# IO_Peripherals.net
KiCad netlist of a schematic drawn in Altium Designer
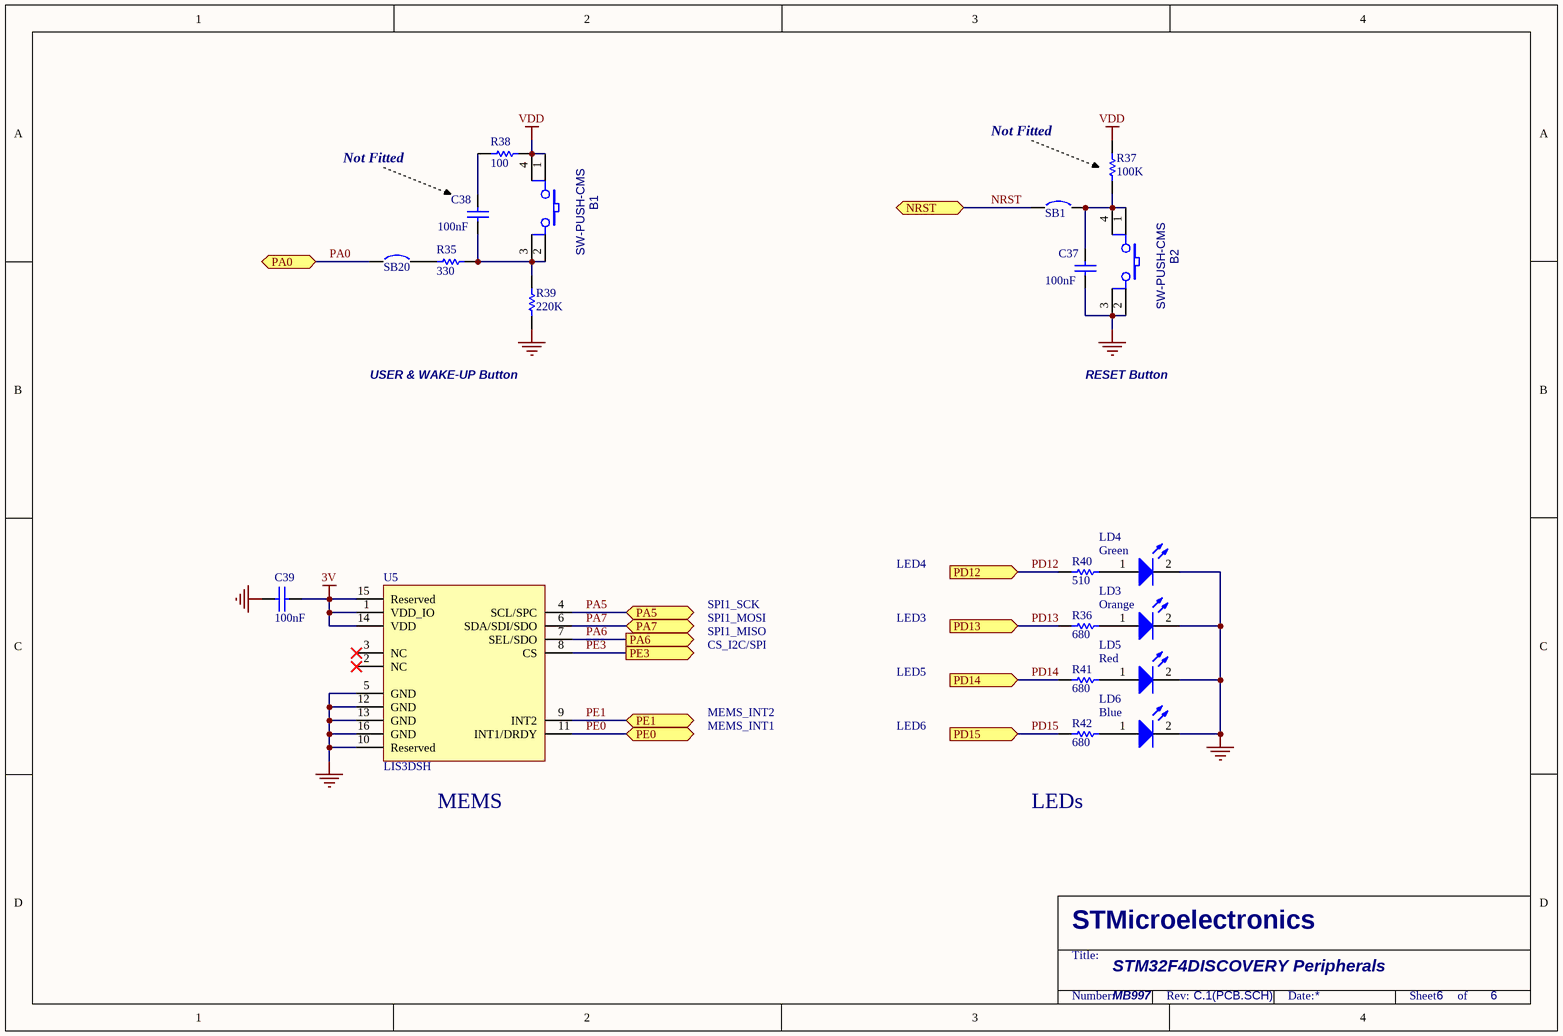
[diagram p0: IO Peripherals.SchDoc]

(export (version "E")
  (design (tool "Eeschema 10.0.6"))
  (components
    (comp (ref "B1")
      (value "SW-PUSH-CMS")
      (footprint "BP1CMS")
      (description "Non-Open Push-Button 0.1A 24V")
      (libsource (lib "MB913_1") (part "SW-PUSH-CMS"))
    )
    (comp (ref "B2")
      (value "SW-PUSH-CMS")
      (footprint "BP1CMS")
      (description "Non-Open Push-Button 0.1A 24V")
      (libsource (lib "MB913_1") (part "SW-PUSH-CMS"))
    )
    (comp (ref "C37")
      (value "100nF")
      (footprint "0603C")
      (description "Capacitor")
      (fields (field (name "PUBLISHER") "Altium Limited"))
      (libsource (lib "Miscellaneous Devices") (part "CAP"))
    )
    (comp (ref "C38")
      (value "100nF")
      (footprint "0603C")
      (description "Capacitor")
      (fields (field (name "PUBLISHER") "Altium Limited"))
      (libsource (lib "Miscellaneous Devices") (part "CAP"))
    )
    (comp (ref "C39")
      (value "100nF")
      (footprint "0402C")
      (description "Capacitor")
      (libsource (lib "*") (part "CAP"))
    )
    (comp (ref "LD3")
      (value "Orange")
      (footprint "0603D")
      (description "Typical RED, GREEN, YELLOW, AMBER GaAs LED")
      (fields (field (name "PUBLISHER") "Altium Limited"))
      (libsource (lib "Miscellaneous Devices") (part "LED2"))
    )
    (comp (ref "LD4")
      (value "Green")
      (footprint "0603D")
      (description "Typical RED, GREEN, YELLOW, AMBER GaAs LED")
      (fields (field (name "PUBLISHER") "Altium Limited"))
      (libsource (lib "Miscellaneous Devices") (part "LED2"))
    )
    (comp (ref "LD5")
      (value "Red")
      (footprint "0603D")
      (description "Typical RED, GREEN, YELLOW, AMBER GaAs LED")
      (fields (field (name "PUBLISHER") "Altium Limited"))
      (libsource (lib "Miscellaneous Devices") (part "LED2"))
    )
    (comp (ref "LD6")
      (value "Blue")
      (footprint "0603D")
      (description "Typical RED, GREEN, YELLOW, AMBER GaAs LED")
      (fields (field (name "PUBLISHER") "Altium Limited"))
      (libsource (lib "Miscellaneous Devices") (part "LED2"))
    )
    (comp (ref "R35")
      (value "330")
      (footprint "0402R")
      (description "Resistor")
      (fields (field (name "PUBLISHER") "Altium Limited"))
      (libsource (lib "Miscellaneous Devices") (part "res1"))
    )
    (comp (ref "R36")
      (value "680")
      (footprint "0603R")
      (description "Resistor")
      (fields (field (name "PUBLISHER") "Altium Limited"))
      (libsource (lib "Miscellaneous Devices") (part "Res1"))
    )
    (comp (ref "R37")
      (value "100K")
      (footprint "0402R")
      (description "Resistor")
      (fields (field (name "PUBLISHER") "Altium Limited"))
      (libsource (lib "Miscellaneous Devices") (part "res1"))
    )
    (comp (ref "R38")
      (value "100")
      (footprint "0402R")
      (description "Resistor")
      (fields (field (name "PUBLISHER") "Altium Limited"))
      (libsource (lib "Miscellaneous Devices") (part "res1"))
    )
    (comp (ref "R39")
      (value "220K")
      (description "Resistor")
      (fields (field (name "PUBLISHER") "Altium Limited"))
      (libsource (lib "Miscellaneous Devices") (part "res1"))
    )
    (comp (ref "R40")
      (value "510")
      (footprint "0603R")
      (description "Resistor")
      (fields (field (name "PUBLISHER") "Altium Limited"))
      (libsource (lib "Miscellaneous Devices") (part "Res1"))
    )
    (comp (ref "R41")
      (value "680")
      (footprint "0603R")
      (description "Resistor")
      (fields (field (name "PUBLISHER") "Altium Limited"))
      (libsource (lib "Miscellaneous Devices") (part "Res1"))
    )
    (comp (ref "R42")
      (value "680")
      (footprint "0603R")
      (description "Resistor")
      (fields (field (name "PUBLISHER") "Altium Limited"))
      (libsource (lib "Miscellaneous Devices") (part "Res1"))
    )
    (comp (ref "SB1")
      (value "Circuit Breaker")
      (footprint "JP2_SMD")
      (fields (field (name "PUBLISHER") "Altium Limited"))
      (libsource (lib "MB915") (part "Circuit Breaker"))
    )
    (comp (ref "SB20")
      (value "Circuit Breaker")
      (footprint "JP2_SMD")
      (fields (field (name "PUBLISHER") "Altium Limited"))
      (libsource (lib "MB915") (part "Circuit Breaker"))
    )
    (comp (ref "U5")
      (value "LIS3DSH")
      (footprint "LGA16(3*3)")
      (description "MEMS motion sensor 3-axis - ±2g to ±16g digital output accelerometer")
      (libsource (lib "MB997") (part "LIS3DSH"))
    )
  )
  (nets
    (net (code "1") (name "/NRST") (class "Default")
      (node (ref "SB1") (pin "1") (pinfunction "1_1") (pintype "passive"))
    )
    (net (code "2") (name "/PA0") (class "Default")
      (node (ref "SB20") (pin "1") (pinfunction "1_1") (pintype "passive"))
    )
    (net (code "3") (name "/PA5") (class "Default")
      (node (ref "U5") (pin "4") (pinfunction "SCL/SPC_4") (pintype "passive"))
    )
    (net (code "4") (name "/PA6") (class "Default")
      (node (ref "U5") (pin "7") (pinfunction "SEL/SDO_7") (pintype "passive"))
    )
    (net (code "5") (name "/PA7") (class "Default")
      (node (ref "U5") (pin "6") (pinfunction "SDA/SDI/SDO_6") (pintype "passive"))
    )
    (net (code "6") (name "/PD12") (class "Default")
      (node (ref "R40") (pin "2") (pinfunction "2_2") (pintype "passive"))
    )
    (net (code "7") (name "/PD13") (class "Default")
      (node (ref "R36") (pin "2") (pinfunction "2_2") (pintype "passive"))
    )
    (net (code "8") (name "/PD14") (class "Default")
      (node (ref "R41") (pin "2") (pinfunction "2_2") (pintype "passive"))
    )
    (net (code "9") (name "/PD15") (class "Default")
      (node (ref "R42") (pin "2") (pinfunction "2_2") (pintype "passive"))
    )
    (net (code "10") (name "/PE0") (class "Default")
      (node (ref "U5") (pin "11") (pinfunction "INT1/DRDY_11") (pintype "passive"))
    )
    (net (code "11") (name "/PE1") (class "Default")
      (node (ref "U5") (pin "9") (pinfunction "INT2_9") (pintype "passive"))
    )
    (net (code "12") (name "/PE3") (class "Default")
      (node (ref "U5") (pin "8") (pinfunction "CS_8") (pintype "passive"))
    )
    (net (code "13") (name "3V") (class "Default")
      (node (ref "C39") (pin "2") (pinfunction "2_2") (pintype "passive"))
      (node (ref "U5") (pin "1") (pinfunction "VDD_IO_1") (pintype "passive"))
      (node (ref "U5") (pin "14") (pinfunction "VDD_14") (pintype "passive"))
      (node (ref "U5") (pin "15") (pinfunction "Reserved_15") (pintype "passive"))
    )
    (net (code "14") (name "GND") (class "Default")
      (node (ref "B2") (pin "2") (pinfunction "2_2") (pintype "passive"))
      (node (ref "B2") (pin "3") (pinfunction "3_3") (pintype "passive"))
      (node (ref "C37") (pin "1") (pinfunction "1_1") (pintype "passive"))
      (node (ref "C39") (pin "1") (pinfunction "1_1") (pintype "passive"))
      (node (ref "LD3") (pin "2") (pinfunction "K_2") (pintype "passive"))
      (node (ref "LD4") (pin "2") (pinfunction "K_2") (pintype "passive"))
      (node (ref "LD5") (pin "2") (pinfunction "K_2") (pintype "passive"))
      (node (ref "LD6") (pin "2") (pinfunction "K_2") (pintype "passive"))
      (node (ref "R39") (pin "1") (pinfunction "1_1") (pintype "passive"))
      (node (ref "U5") (pin "10") (pinfunction "Reserved_10") (pintype "passive"))
      (node (ref "U5") (pin "12") (pinfunction "GND_12") (pintype "passive"))
      (node (ref "U5") (pin "13") (pinfunction "GND_13") (pintype "passive"))
      (node (ref "U5") (pin "16") (pinfunction "GND_16") (pintype "passive"))
      (node (ref "U5") (pin "5") (pinfunction "GND_5") (pintype "passive"))
    )
    (net (code "15") (name "Net-(B1-Pad2)") (class "Default")
      (node (ref "B1") (pin "2") (pinfunction "2_2") (pintype "passive"))
      (node (ref "B1") (pin "3") (pinfunction "3_3") (pintype "passive"))
      (node (ref "C38") (pin "1") (pinfunction "1_1") (pintype "passive"))
      (node (ref "R35") (pin "2") (pinfunction "2_2") (pintype "passive"))
      (node (ref "R39") (pin "2") (pinfunction "2_2") (pintype "passive"))
    )
    (net (code "16") (name "Net-(B2-Pad1)") (class "Default")
      (node (ref "B2") (pin "1") (pinfunction "1_1") (pintype "passive"))
      (node (ref "B2") (pin "4") (pinfunction "4_4") (pintype "passive"))
      (node (ref "C37") (pin "2") (pinfunction "2_2") (pintype "passive"))
      (node (ref "R37") (pin "1") (pinfunction "1_1") (pintype "passive"))
      (node (ref "SB1") (pin "2") (pinfunction "2_2") (pintype "passive"))
    )
    (net (code "17") (name "Net-(C38-Pad2)") (class "Default")
      (node (ref "C38") (pin "2") (pinfunction "2_2") (pintype "passive"))
      (node (ref "R38") (pin "1") (pinfunction "1_1") (pintype "passive"))
    )
    (net (code "18") (name "Net-(LD3-A)") (class "Default")
      (node (ref "LD3") (pin "1") (pinfunction "A_1") (pintype "passive"))
      (node (ref "R36") (pin "1") (pinfunction "1_1") (pintype "passive"))
    )
    (net (code "19") (name "Net-(LD4-A)") (class "Default")
      (node (ref "LD4") (pin "1") (pinfunction "A_1") (pintype "passive"))
      (node (ref "R40") (pin "1") (pinfunction "1_1") (pintype "passive"))
    )
    (net (code "20") (name "Net-(LD5-A)") (class "Default")
      (node (ref "LD5") (pin "1") (pinfunction "A_1") (pintype "passive"))
      (node (ref "R41") (pin "1") (pinfunction "1_1") (pintype "passive"))
    )
    (net (code "21") (name "Net-(LD6-A)") (class "Default")
      (node (ref "LD6") (pin "1") (pinfunction "A_1") (pintype "passive"))
      (node (ref "R42") (pin "1") (pinfunction "1_1") (pintype "passive"))
    )
    (net (code "22") (name "Net-(R35-Pad1)") (class "Default")
      (node (ref "R35") (pin "1") (pinfunction "1_1") (pintype "passive"))
      (node (ref "SB20") (pin "2") (pinfunction "2_2") (pintype "passive"))
    )
    (net (code "23") (name "VDD") (class "Default")
      (node (ref "B1") (pin "1") (pinfunction "1_1") (pintype "passive"))
      (node (ref "B1") (pin "4") (pinfunction "4_4") (pintype "passive"))
      (node (ref "R37") (pin "2") (pinfunction "2_2") (pintype "passive"))
      (node (ref "R38") (pin "2") (pinfunction "2_2") (pintype "passive"))
    )
    (net (code "24") (name "unconnected-(U5-NC-Pad2)") (class "Default")
      (node (ref "U5") (pin "2") (pinfunction "NC_2") (pintype "passive+no_connect"))
    )
    (net (code "25") (name "unconnected-(U5-NC-Pad3)") (class "Default")
      (node (ref "U5") (pin "3") (pinfunction "NC_3") (pintype "passive+no_connect"))
    )
  )
)
